# Connectors.net
KiCad netlist of a schematic drawn in Altium Designer
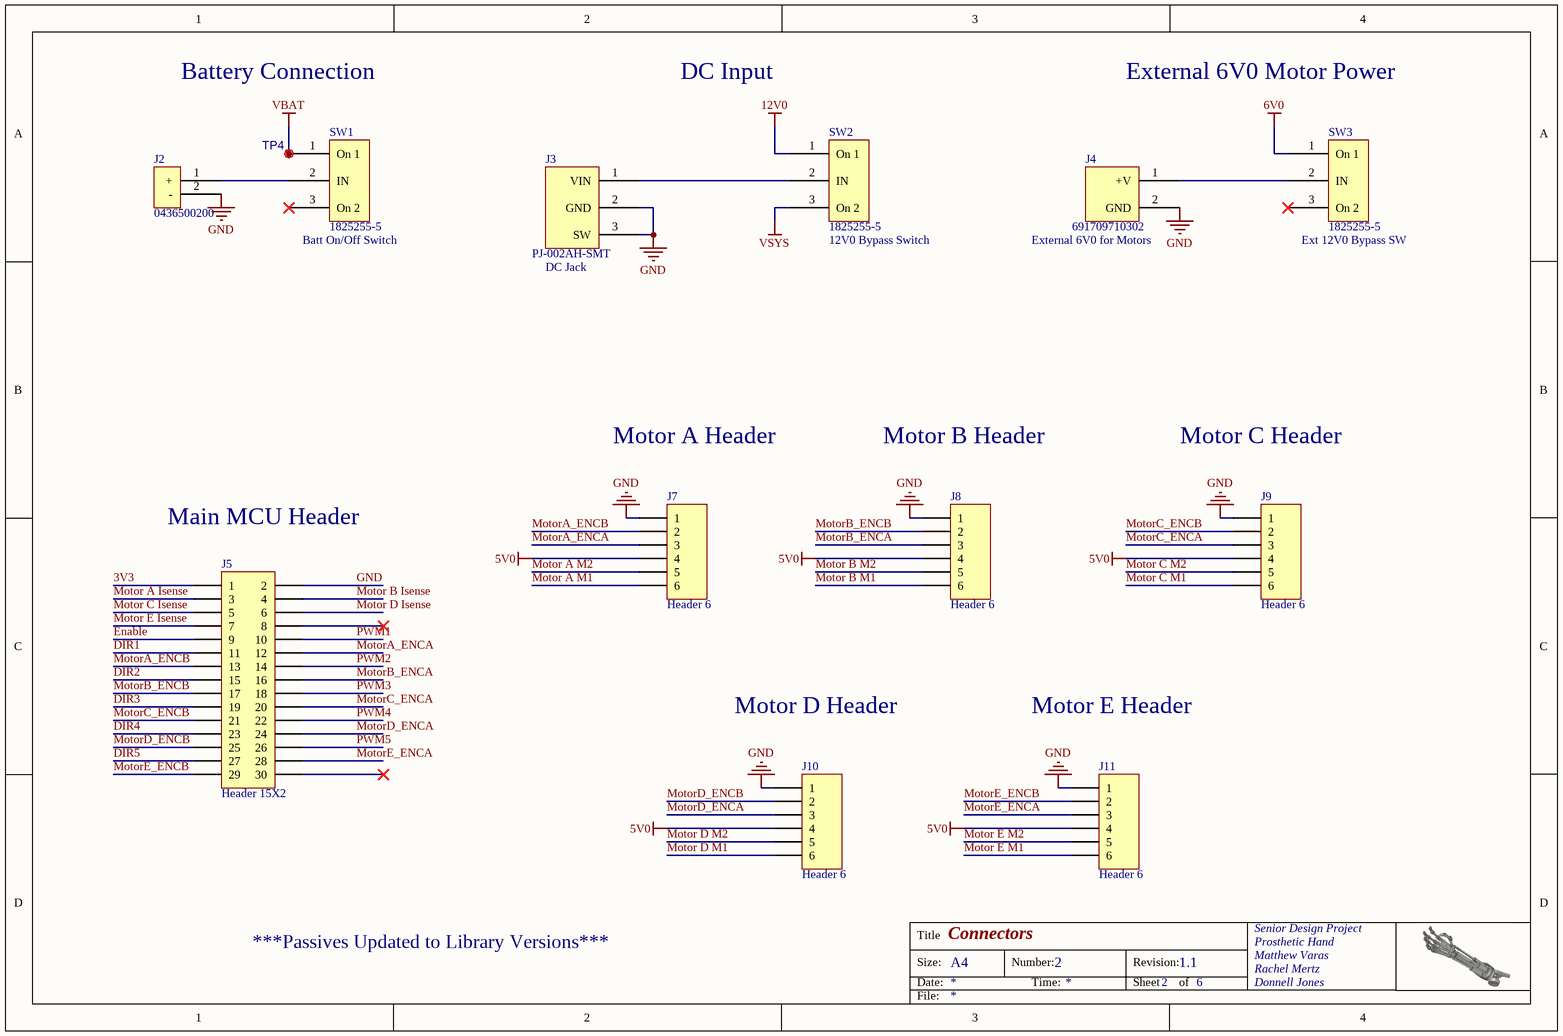
[diagram p0: Connectors.SchDoc]

(export (version "E")
  (design (tool "Eeschema 10.0.6"))
  (components
    (comp (ref "J2")
      (value "0436500200")
      (footprint "43650-0200")
      (description "CONN HEADER 2POS 3MM RT ANG TIN")
      (libsource (lib "Prosthetic Hand Schematic Lib") (part "Battery Connector"))
    )
    (comp (ref "J3")
      (value "PJ-002AH-SMT")
      (footprint "PJ-002AH-SMT")
      (description "CONN POWER JACK 2.1X5.5MM HI CUR")
      (fields (field (name "ALTIUM_UNNAMED_1") "DC Jack"))
      (libsource (lib "Prosthetic Hand Schematic Lib") (part "PJ-002AH-SMT"))
    )
    (comp (ref "J4")
      (value "691709710302")
      (footprint "2-Pin Screw Terminal")
      (description "CONN TERM BLOCK 2POS 5MM BLACK")
      (fields (field (name "ALTIUM_UNNAMED_1") "External 6V0 for Motors"))
      (libsource (lib "Prosthetic Hand Schematic Lib") (part "Screw Terminal 2-pin"))
    )
    (comp (ref "J5")
      (value "Header 15X2")
      (footprint "HDR2X15")
      (description "30 Position Receptacle Connector 0.100\" (2.54mm) Through Hole Tin")
      (libsource (lib "Prosthetic Hand Schematic Lib") (part "Header 15X2"))
    )
    (comp (ref "J7")
      (value "Header 6")
      (footprint "HDR1X6")
      (description "6 Positions Header, Unshrouded Connector 0.100\" (2.54mm) Through Hole Tin")
      (libsource (lib "Prosthetic Hand Schematic Lib") (part "Header 6"))
    )
    (comp (ref "J8")
      (value "Header 6")
      (footprint "HDR1X6")
      (description "6 Positions Header, Unshrouded Connector 0.100\" (2.54mm) Through Hole Tin")
      (libsource (lib "Prosthetic Hand Schematic Lib") (part "Header 6"))
    )
    (comp (ref "J9")
      (value "Header 6")
      (footprint "HDR1X6")
      (description "6 Positions Header, Unshrouded Connector 0.100\" (2.54mm) Through Hole Tin")
      (libsource (lib "Prosthetic Hand Schematic Lib") (part "Header 6"))
    )
    (comp (ref "J10")
      (value "Header 6")
      (footprint "HDR1X6")
      (description "6 Positions Header, Unshrouded Connector 0.100\" (2.54mm) Through Hole Tin")
      (libsource (lib "Prosthetic Hand Schematic Lib") (part "Header 6"))
    )
    (comp (ref "J11")
      (value "Header 6")
      (footprint "HDR1X6")
      (description "6 Positions Header, Unshrouded Connector 0.100\" (2.54mm) Through Hole Tin")
      (libsource (lib "Prosthetic Hand Schematic Lib") (part "Header 6"))
    )
    (comp (ref "SW1")
      (value "1825255-5")
      (footprint "On/Off/On Slider Switch")
      (description "SWITCH SLIDE SPDT 300MA 125V")
      (fields (field (name "ALTIUM_UNNAMED_1") "Batt On/Off Switch"))
      (libsource (lib "Prosthetic Hand Schematic Lib") (part "1825255-5"))
    )
    (comp (ref "SW2")
      (value "1825255-5")
      (footprint "On/Off/On Slider Switch")
      (description "SWITCH SLIDE SPDT 300MA 125V")
      (fields (field (name "ALTIUM_UNNAMED_1") "12V0 Bypass Switch"))
      (libsource (lib "Prosthetic Hand Schematic Lib") (part "1825255-5"))
    )
    (comp (ref "SW3")
      (value "1825255-5")
      (footprint "On/Off/On Slider Switch")
      (description "SWITCH SLIDE SPDT 300MA 125V")
      (fields (field (name "ALTIUM_UNNAMED_1") "Ext 12V0 Bypass SW"))
      (libsource (lib "Prosthetic Hand Schematic Lib") (part "1825255-5"))
    )
    (comp (ref "TP4")
      (value "Test Point")
      (footprint "Testpoint_70")
      (description "Test Pad")
      (libsource (lib "Prosthetic Hand Schematic Lib") (part "Test Point"))
    )
  )
  (nets
    (net (code "1") (name "/3V3") (class "Default")
      (node (ref "J5") (pin "1") (pinfunction "1_1") (pintype "passive"))
    )
    (net (code "2") (name "/DIR1") (class "Default")
      (node (ref "J5") (pin "11") (pinfunction "11_11") (pintype "passive"))
    )
    (net (code "3") (name "/DIR2") (class "Default")
      (node (ref "J5") (pin "15") (pinfunction "15_15") (pintype "passive"))
    )
    (net (code "4") (name "/DIR3") (class "Default")
      (node (ref "J5") (pin "19") (pinfunction "19_19") (pintype "passive"))
    )
    (net (code "5") (name "/DIR4") (class "Default")
      (node (ref "J5") (pin "23") (pinfunction "23_23") (pintype "passive"))
    )
    (net (code "6") (name "/DIR5") (class "Default")
      (node (ref "J5") (pin "27") (pinfunction "27_27") (pintype "passive"))
    )
    (net (code "7") (name "/Enable") (class "Default")
      (node (ref "J5") (pin "9") (pinfunction "9_9") (pintype "passive"))
    )
    (net (code "8") (name "/Motor A Isense") (class "Default")
      (node (ref "J5") (pin "3") (pinfunction "3_3") (pintype "passive"))
    )
    (net (code "9") (name "/Motor A M1") (class "Default")
      (node (ref "J7") (pin "6") (pinfunction "6_6") (pintype "passive"))
    )
    (net (code "10") (name "/Motor A M2") (class "Default")
      (node (ref "J7") (pin "5") (pinfunction "5_5") (pintype "passive"))
    )
    (net (code "11") (name "/Motor B Isense") (class "Default")
      (node (ref "J5") (pin "4") (pinfunction "4_4") (pintype "passive"))
    )
    (net (code "12") (name "/Motor B M1") (class "Default")
      (node (ref "J8") (pin "6") (pinfunction "6_6") (pintype "passive"))
    )
    (net (code "13") (name "/Motor B M2") (class "Default")
      (node (ref "J8") (pin "5") (pinfunction "5_5") (pintype "passive"))
    )
    (net (code "14") (name "/Motor C Isense") (class "Default")
      (node (ref "J5") (pin "5") (pinfunction "5_5") (pintype "passive"))
    )
    (net (code "15") (name "/Motor C M1") (class "Default")
      (node (ref "J9") (pin "6") (pinfunction "6_6") (pintype "passive"))
    )
    (net (code "16") (name "/Motor C M2") (class "Default")
      (node (ref "J9") (pin "5") (pinfunction "5_5") (pintype "passive"))
    )
    (net (code "17") (name "/Motor D Isense") (class "Default")
      (node (ref "J5") (pin "6") (pinfunction "6_6") (pintype "passive"))
    )
    (net (code "18") (name "/Motor D M1") (class "Default")
      (node (ref "J10") (pin "6") (pinfunction "6_6") (pintype "passive"))
    )
    (net (code "19") (name "/Motor D M2") (class "Default")
      (node (ref "J10") (pin "5") (pinfunction "5_5") (pintype "passive"))
    )
    (net (code "20") (name "/Motor E Isense") (class "Default")
      (node (ref "J5") (pin "7") (pinfunction "7_7") (pintype "passive"))
    )
    (net (code "21") (name "/Motor E M1") (class "Default")
      (node (ref "J11") (pin "6") (pinfunction "6_6") (pintype "passive"))
    )
    (net (code "22") (name "/Motor E M2") (class "Default")
      (node (ref "J11") (pin "5") (pinfunction "5_5") (pintype "passive"))
    )
    (net (code "23") (name "/MotorA_ENCA") (class "Default")
      (node (ref "J5") (pin "12") (pinfunction "12_12") (pintype "passive"))
      (node (ref "J7") (pin "3") (pinfunction "3_3") (pintype "passive"))
    )
    (net (code "24") (name "/MotorA_ENCB") (class "Default")
      (node (ref "J5") (pin "13") (pinfunction "13_13") (pintype "passive"))
      (node (ref "J7") (pin "2") (pinfunction "2_2") (pintype "passive"))
    )
    (net (code "25") (name "/MotorB_ENCA") (class "Default")
      (node (ref "J5") (pin "16") (pinfunction "16_16") (pintype "passive"))
      (node (ref "J8") (pin "3") (pinfunction "3_3") (pintype "passive"))
    )
    (net (code "26") (name "/MotorB_ENCB") (class "Default")
      (node (ref "J5") (pin "17") (pinfunction "17_17") (pintype "passive"))
      (node (ref "J8") (pin "2") (pinfunction "2_2") (pintype "passive"))
    )
    (net (code "27") (name "/MotorC_ENCA") (class "Default")
      (node (ref "J5") (pin "20") (pinfunction "20_20") (pintype "passive"))
      (node (ref "J9") (pin "3") (pinfunction "3_3") (pintype "passive"))
    )
    (net (code "28") (name "/MotorC_ENCB") (class "Default")
      (node (ref "J5") (pin "21") (pinfunction "21_21") (pintype "passive"))
      (node (ref "J9") (pin "2") (pinfunction "2_2") (pintype "passive"))
    )
    (net (code "29") (name "/MotorD_ENCA") (class "Default")
      (node (ref "J10") (pin "3") (pinfunction "3_3") (pintype "passive"))
      (node (ref "J5") (pin "24") (pinfunction "24_24") (pintype "passive"))
    )
    (net (code "30") (name "/MotorD_ENCB") (class "Default")
      (node (ref "J10") (pin "2") (pinfunction "2_2") (pintype "passive"))
      (node (ref "J5") (pin "25") (pinfunction "25_25") (pintype "passive"))
    )
    (net (code "31") (name "/MotorE_ENCA") (class "Default")
      (node (ref "J11") (pin "3") (pinfunction "3_3") (pintype "passive"))
      (node (ref "J5") (pin "28") (pinfunction "28_28") (pintype "passive"))
    )
    (net (code "32") (name "/MotorE_ENCB") (class "Default")
      (node (ref "J11") (pin "2") (pinfunction "2_2") (pintype "passive"))
      (node (ref "J5") (pin "29") (pinfunction "29_29") (pintype "passive"))
    )
    (net (code "33") (name "/PWM1") (class "Default")
      (node (ref "J5") (pin "10") (pinfunction "10_10") (pintype "passive"))
    )
    (net (code "34") (name "/PWM2") (class "Default")
      (node (ref "J5") (pin "14") (pinfunction "14_14") (pintype "passive"))
    )
    (net (code "35") (name "/PWM3") (class "Default")
      (node (ref "J5") (pin "18") (pinfunction "18_18") (pintype "passive"))
    )
    (net (code "36") (name "/PWM4") (class "Default")
      (node (ref "J5") (pin "22") (pinfunction "22_22") (pintype "passive"))
    )
    (net (code "37") (name "/PWM5") (class "Default")
      (node (ref "J5") (pin "26") (pinfunction "26_26") (pintype "passive"))
    )
    (net (code "38") (name "5V0") (class "Default")
      (node (ref "J10") (pin "4") (pinfunction "4_4") (pintype "passive"))
      (node (ref "J11") (pin "4") (pinfunction "4_4") (pintype "passive"))
      (node (ref "J7") (pin "4") (pinfunction "4_4") (pintype "passive"))
      (node (ref "J8") (pin "4") (pinfunction "4_4") (pintype "passive"))
      (node (ref "J9") (pin "4") (pinfunction "4_4") (pintype "passive"))
    )
    (net (code "39") (name "6V0") (class "Default")
      (node (ref "SW3") (pin "1") (pinfunction "On_1_1") (pintype "passive"))
    )
    (net (code "40") (name "12V0") (class "Default")
      (node (ref "SW2") (pin "1") (pinfunction "On_1_1") (pintype "passive"))
    )
    (net (code "41") (name "GND") (class "Default")
      (node (ref "J10") (pin "1") (pinfunction "1_1") (pintype "passive"))
      (node (ref "J11") (pin "1") (pinfunction "1_1") (pintype "passive"))
      (node (ref "J2") (pin "2") (pinfunction "-_2") (pintype "passive"))
      (node (ref "J3") (pin "2") (pinfunction "GND_2") (pintype "passive"))
      (node (ref "J3") (pin "3") (pinfunction "SW_3") (pintype "passive"))
      (node (ref "J4") (pin "2") (pinfunction "GND_2") (pintype "passive"))
      (node (ref "J5") (pin "2") (pinfunction "2_2") (pintype "passive"))
      (node (ref "J7") (pin "1") (pinfunction "1_1") (pintype "passive"))
      (node (ref "J8") (pin "1") (pinfunction "1_1") (pintype "passive"))
      (node (ref "J9") (pin "1") (pinfunction "1_1") (pintype "passive"))
    )
    (net (code "42") (name "Net-(J2-+)") (class "Default")
      (node (ref "J2") (pin "1") (pinfunction "+_1") (pintype "passive"))
      (node (ref "SW1") (pin "2") (pinfunction "IN_2") (pintype "passive"))
    )
    (net (code "43") (name "Net-(J3-VIN)") (class "Default")
      (node (ref "J3") (pin "1") (pinfunction "VIN_1") (pintype "passive"))
      (node (ref "SW2") (pin "2") (pinfunction "IN_2") (pintype "passive"))
    )
    (net (code "44") (name "Net-(J4-+V)") (class "Default")
      (node (ref "J4") (pin "1") (pinfunction "+V_1") (pintype "passive"))
      (node (ref "SW3") (pin "2") (pinfunction "IN_2") (pintype "passive"))
    )
    (net (code "45") (name "VBAT") (class "Default")
      (node (ref "SW1") (pin "1") (pinfunction "On_1_1") (pintype "passive"))
      (node (ref "TP4") (pin "1") (pinfunction "M80_1") (pintype "passive"))
    )
    (net (code "46") (name "VSYS") (class "Default")
      (node (ref "SW2") (pin "3") (pinfunction "On_2_3") (pintype "passive"))
    )
    (net (code "47") (name "unconnected-(J5-Pad8)") (class "Default")
      (node (ref "J5") (pin "8") (pinfunction "8_8") (pintype "passive+no_connect"))
    )
    (net (code "48") (name "unconnected-(J5-Pad30)") (class "Default")
      (node (ref "J5") (pin "30") (pinfunction "30_30") (pintype "passive+no_connect"))
    )
    (net (code "49") (name "unconnected-(SW1-On_2-Pad3)") (class "Default")
      (node (ref "SW1") (pin "3") (pinfunction "On_2_3") (pintype "passive+no_connect"))
    )
    (net (code "50") (name "unconnected-(SW3-On_2-Pad3)") (class "Default")
      (node (ref "SW3") (pin "3") (pinfunction "On_2_3") (pintype "passive+no_connect"))
    )
  )
)
